# main.net
KiCad netlist of a schematic drawn in Altium Designer
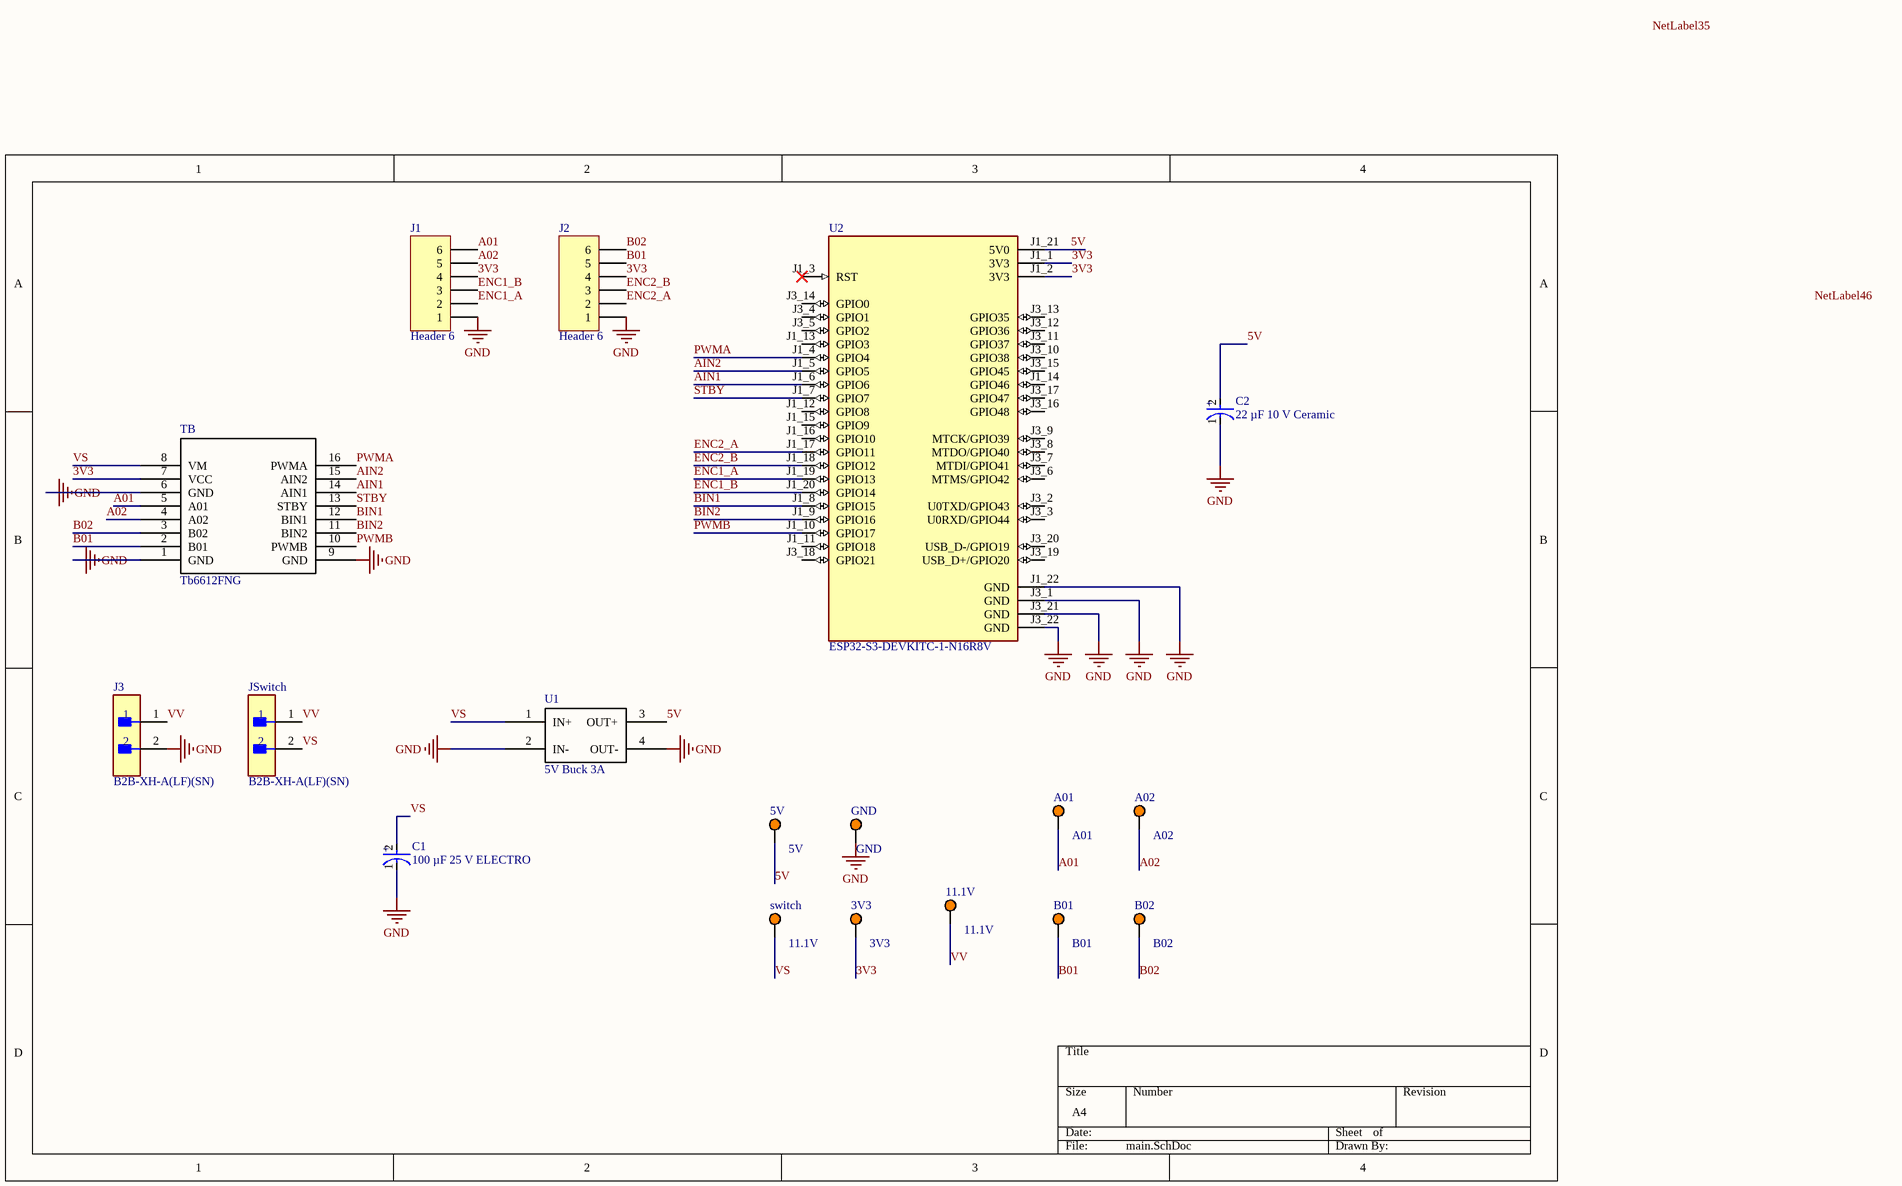
[diagram p0: main.SchDoc]

(export (version "E")
  (design (tool "Eeschema 10.0.6"))
  (components
    (comp (ref "3V3")
      (value "3V3")
      (footprint "Test-Pin-TH")
      (description "Test pin TH generic")
      (libsource (lib "UGs@UoA") (part "Test Pin"))
    )
    (comp (ref "5V")
      (value "5V")
      (footprint "Test-Pin-TH")
      (description "Test pin TH generic")
      (libsource (lib "UGs@UoA") (part "Test Pin"))
    )
    (comp (ref "11.1V")
      (value "11.1V")
      (footprint "Test-Pin-TH")
      (description "Test pin TH generic")
      (libsource (lib "UGs@UoA") (part "Test Pin"))
    )
    (comp (ref "A01")
      (value "A01")
      (footprint "Test-Pin-TH")
      (description "Test pin TH generic")
      (libsource (lib "UGs@UoA") (part "Test Pin"))
    )
    (comp (ref "A02")
      (value "A02")
      (footprint "Test-Pin-TH")
      (description "Test pin TH generic")
      (libsource (lib "UGs@UoA") (part "Test Pin"))
    )
    (comp (ref "B01")
      (value "B01")
      (footprint "Test-Pin-TH")
      (description "Test pin TH generic")
      (libsource (lib "UGs@UoA") (part "Test Pin"))
    )
    (comp (ref "B02")
      (value "B02")
      (footprint "Test-Pin-TH")
      (description "Test pin TH generic")
      (libsource (lib "UGs@UoA") (part "Test Pin"))
    )
    (comp (ref "C1")
      (value "100 µF 25 V ELECTRO")
      (footprint "FP-RAD-TH-D_6_3_0_5-L_11-MFG")
      (description "Aluminum Electrolytic Capacitors (Radial Lead Type) 100uF ±20% 25V")
      (libsource (lib "Altium Content Vault") (part "a00bbbee19879c290e62620ae7e47b1"))
    )
    (comp (ref "C2")
      (value "22 µF 10 V Ceramic")
      (footprint "FP-RAD-TH-D_6_3_0_5-L_11-MFG")
      (description "Aluminum Electrolytic Capacitors (Radial Lead Type) 100uF ±20% 25V")
      (libsource (lib "Altium Content Vault") (part "a00bbbee19879c290e62620ae7e47b1"))
    )
    (comp (ref "GND")
      (value "GND")
      (footprint "Test-Pin-TH")
      (description "Test pin TH generic")
      (libsource (lib "UGs@UoA") (part "Test Pin"))
    )
    (comp (ref "J1")
      (value "Header 6")
      (footprint "HDR1X6")
      (description "Header, 6-Pin")
      (fields (field (name "PUBLISHER") "Altium Limited"))
      (libsource (lib "Miscellaneous Connectors") (part "Header 6"))
    )
    (comp (ref "J2")
      (value "Header 6")
      (footprint "HDR1X6")
      (description "Header, 6-Pin")
      (fields (field (name "PUBLISHER") "Altium Limited"))
      (libsource (lib "Miscellaneous Connectors") (part "Header 6"))
    )
    (comp (ref "J3")
      (value "B2B-XH-A(LF)(SN)")
      (footprint "FP-B2B-XH-A_LF_SN-MFG")
      (description "CONN HEADER VERT 2POS 2.5MM")
      (libsource (lib "Altium Content Vault") (part "3bc925449376181038e59eaffc5286c"))
    )
    (comp (ref "JSwitch")
      (value "B2B-XH-A(LF)(SN)")
      (footprint "FP-B2B-XH-A_LF_SN-MFG")
      (description "CONN HEADER VERT 2POS 2.5MM")
      (libsource (lib "Altium Content Vault") (part "3bc925449376181038e59eaffc5286c"))
    )
    (comp (ref "switch")
      (value "11.1V")
      (footprint "Test-Pin-TH")
      (description "Test pin TH generic")
      (libsource (lib "UGs@UoA") (part "Test Pin"))
    )
    (comp (ref "TB") (value "Tb6612FNG") (footprint "TB6612FNG") (libsource (lib "parts") (part "Tb6612FNG")))
    (comp (ref "U1")
      (value "5V Buck 3A")
      (footprint "BUCK_MINI_3A")
      (libsource (lib "parts") (part "BUCK_5V_3A"))
    )
    (comp (ref "U2")
      (value "ESP32-S3-DEVKITC-1-N16R8V")
      (footprint "XCVR_ESP32-S3-DEVKITC-1-N16R8V")
      (fields (field (name "MF") "Espressif Systems"))
      (libsource (lib "ESP32-S3-DEVKITC-1-N16R8V") (part "ESP32-S3-DEVKITC-1-N16R8V"))
    )
  )
  (nets
    (net (code "1") (name "/3V3") (class "Default")
      (node (ref "3V3") (pin "1") (pinfunction "1_1") (pintype "passive"))
      (node (ref "J1") (pin "4") (pinfunction "4_4") (pintype "passive"))
      (node (ref "J2") (pin "4") (pinfunction "4_4") (pintype "passive"))
      (node (ref "TB") (pin "7") (pinfunction "VCC_7") (pintype "passive"))
      (node (ref "U2") (pin "J1_1") (pinfunction "3V3_J1_1") (pintype "power_in"))
      (node (ref "U2") (pin "J1_2") (pinfunction "3V3_J1_2") (pintype "power_in"))
    )
    (net (code "2") (name "/5V") (class "Default")
      (node (ref "5V") (pin "1") (pinfunction "1_1") (pintype "passive"))
      (node (ref "C2") (pin "2") (pinfunction "A_2") (pintype "passive"))
      (node (ref "U1") (pin "3") (pinfunction "OUT+_3") (pintype "passive"))
      (node (ref "U2") (pin "J1_21") (pinfunction "5V0_J1_21") (pintype "power_in"))
    )
    (net (code "3") (name "/A01") (class "Default")
      (node (ref "A01") (pin "1") (pinfunction "1_1") (pintype "passive"))
      (node (ref "J1") (pin "6") (pinfunction "6_6") (pintype "passive"))
      (node (ref "TB") (pin "5") (pinfunction "A01_5") (pintype "passive"))
    )
    (net (code "4") (name "/A02") (class "Default")
      (node (ref "A02") (pin "1") (pinfunction "1_1") (pintype "passive"))
      (node (ref "J1") (pin "5") (pinfunction "5_5") (pintype "passive"))
      (node (ref "TB") (pin "4") (pinfunction "A02_4") (pintype "passive"))
    )
    (net (code "5") (name "/AIN1") (class "Default")
      (node (ref "TB") (pin "14") (pinfunction "AIN1_14") (pintype "passive"))
      (node (ref "U2") (pin "J1_6") (pinfunction "GPIO6_J1_6") (pintype "bidirectional"))
    )
    (net (code "6") (name "/AIN2") (class "Default")
      (node (ref "TB") (pin "15") (pinfunction "AIN2_15") (pintype "passive"))
      (node (ref "U2") (pin "J1_5") (pinfunction "GPIO5_J1_5") (pintype "bidirectional"))
    )
    (net (code "7") (name "/B01") (class "Default")
      (node (ref "B01") (pin "1") (pinfunction "1_1") (pintype "passive"))
      (node (ref "J2") (pin "5") (pinfunction "5_5") (pintype "passive"))
      (node (ref "TB") (pin "2") (pinfunction "B01_2") (pintype "passive"))
    )
    (net (code "8") (name "/B02") (class "Default")
      (node (ref "B02") (pin "1") (pinfunction "1_1") (pintype "passive"))
      (node (ref "J2") (pin "6") (pinfunction "6_6") (pintype "passive"))
      (node (ref "TB") (pin "3") (pinfunction "B02_3") (pintype "passive"))
    )
    (net (code "9") (name "/BIN1") (class "Default")
      (node (ref "TB") (pin "12") (pinfunction "BIN1_12") (pintype "passive"))
      (node (ref "U2") (pin "J1_8") (pinfunction "GPIO15_J1_8") (pintype "bidirectional"))
    )
    (net (code "10") (name "/BIN2") (class "Default")
      (node (ref "TB") (pin "11") (pinfunction "BIN2_11") (pintype "passive"))
      (node (ref "U2") (pin "J1_9") (pinfunction "GPIO16_J1_9") (pintype "bidirectional"))
    )
    (net (code "11") (name "/ENC1_A") (class "Default")
      (node (ref "J1") (pin "2") (pinfunction "2_2") (pintype "passive"))
      (node (ref "U2") (pin "J1_19") (pinfunction "GPIO13_J1_19") (pintype "bidirectional"))
    )
    (net (code "12") (name "/ENC1_B") (class "Default")
      (node (ref "J1") (pin "3") (pinfunction "3_3") (pintype "passive"))
      (node (ref "U2") (pin "J1_20") (pinfunction "GPIO14_J1_20") (pintype "bidirectional"))
    )
    (net (code "13") (name "/ENC2_A") (class "Default")
      (node (ref "J2") (pin "2") (pinfunction "2_2") (pintype "passive"))
      (node (ref "U2") (pin "J1_17") (pinfunction "GPIO11_J1_17") (pintype "bidirectional"))
    )
    (net (code "14") (name "/ENC2_B") (class "Default")
      (node (ref "J2") (pin "3") (pinfunction "3_3") (pintype "passive"))
      (node (ref "U2") (pin "J1_18") (pinfunction "GPIO12_J1_18") (pintype "bidirectional"))
    )
    (net (code "17") (name "/PWMA") (class "Default")
      (node (ref "TB") (pin "16") (pinfunction "PWMA_16") (pintype "passive"))
      (node (ref "U2") (pin "J1_4") (pinfunction "GPIO4_J1_4") (pintype "bidirectional"))
    )
    (net (code "18") (name "/PWMB") (class "Default")
      (node (ref "TB") (pin "10") (pinfunction "PWMB_10") (pintype "passive"))
      (node (ref "U2") (pin "J1_10") (pinfunction "GPIO17_J1_10") (pintype "bidirectional"))
    )
    (net (code "19") (name "/STBY") (class "Default")
      (node (ref "TB") (pin "13") (pinfunction "STBY_13") (pintype "passive"))
      (node (ref "U2") (pin "J1_7") (pinfunction "GPIO7_J1_7") (pintype "bidirectional"))
    )
    (net (code "20") (name "/VS") (class "Default")
      (node (ref "C1") (pin "2") (pinfunction "A_2") (pintype "passive"))
      (node (ref "JSwitch") (pin "2") (pinfunction "2_2") (pintype "passive"))
      (node (ref "TB") (pin "8") (pinfunction "VM_8") (pintype "passive"))
      (node (ref "U1") (pin "1") (pinfunction "IN+_1") (pintype "passive"))
      (node (ref "switch") (pin "1") (pinfunction "1_1") (pintype "passive"))
    )
    (net (code "21") (name "/VV") (class "Default")
      (node (ref "11.1V") (pin "1") (pinfunction "1_1") (pintype "passive"))
      (node (ref "J3") (pin "1") (pinfunction "1_1") (pintype "passive"))
      (node (ref "JSwitch") (pin "1") (pinfunction "1_1") (pintype "passive"))
    )
    (net (code "22") (name "GND") (class "Default")
      (node (ref "C1") (pin "1") (pinfunction "C_1") (pintype "passive"))
      (node (ref "C2") (pin "1") (pinfunction "C_1") (pintype "passive"))
      (node (ref "GND") (pin "1") (pinfunction "1_1") (pintype "passive"))
      (node (ref "J1") (pin "1") (pinfunction "1_1") (pintype "passive"))
      (node (ref "J2") (pin "1") (pinfunction "1_1") (pintype "passive"))
      (node (ref "J3") (pin "2") (pinfunction "2_2") (pintype "passive"))
      (node (ref "TB") (pin "1") (pinfunction "GND_1") (pintype "passive"))
      (node (ref "TB") (pin "6") (pinfunction "GND_6") (pintype "passive"))
      (node (ref "TB") (pin "9") (pinfunction "GND_9") (pintype "passive"))
      (node (ref "U1") (pin "2") (pinfunction "IN-_2") (pintype "passive"))
      (node (ref "U1") (pin "4") (pinfunction "OUT-_4") (pintype "passive"))
      (node (ref "U2") (pin "J1_22") (pinfunction "GND_J1_22") (pintype "power_in"))
      (node (ref "U2") (pin "J3_1") (pinfunction "GND_J3_1") (pintype "power_in"))
      (node (ref "U2") (pin "J3_21") (pinfunction "GND_J3_21") (pintype "power_in"))
      (node (ref "U2") (pin "J3_22") (pinfunction "GND_J3_22") (pintype "power_in"))
    )
    (net (code "23") (name "unconnected-(U2-GPIO0-PadJ3_14)") (class "Default")
      (node (ref "U2") (pin "J3_14") (pinfunction "GPIO0_J3_14") (pintype "bidirectional"))
    )
    (net (code "24") (name "unconnected-(U2-GPIO1-PadJ3_4)") (class "Default")
      (node (ref "U2") (pin "J3_4") (pinfunction "GPIO1_J3_4") (pintype "bidirectional"))
    )
    (net (code "25") (name "unconnected-(U2-GPIO2-PadJ3_5)") (class "Default")
      (node (ref "U2") (pin "J3_5") (pinfunction "GPIO2_J3_5") (pintype "bidirectional"))
    )
    (net (code "26") (name "unconnected-(U2-GPIO3-PadJ1_13)") (class "Default")
      (node (ref "U2") (pin "J1_13") (pinfunction "GPIO3_J1_13") (pintype "bidirectional"))
    )
    (net (code "27") (name "unconnected-(U2-GPIO8-PadJ1_12)") (class "Default")
      (node (ref "U2") (pin "J1_12") (pinfunction "GPIO8_J1_12") (pintype "bidirectional"))
    )
    (net (code "28") (name "unconnected-(U2-GPIO9-PadJ1_15)") (class "Default")
      (node (ref "U2") (pin "J1_15") (pinfunction "GPIO9_J1_15") (pintype "bidirectional"))
    )
    (net (code "29") (name "unconnected-(U2-GPIO10-PadJ1_16)") (class "Default")
      (node (ref "U2") (pin "J1_16") (pinfunction "GPIO10_J1_16") (pintype "bidirectional"))
    )
    (net (code "30") (name "unconnected-(U2-GPIO18-PadJ1_11)") (class "Default")
      (node (ref "U2") (pin "J1_11") (pinfunction "GPIO18_J1_11") (pintype "bidirectional"))
    )
    (net (code "31") (name "unconnected-(U2-GPIO21-PadJ3_18)") (class "Default")
      (node (ref "U2") (pin "J3_18") (pinfunction "GPIO21_J3_18") (pintype "bidirectional"))
    )
    (net (code "32") (name "unconnected-(U2-GPIO35-PadJ3_13)") (class "Default")
      (node (ref "U2") (pin "J3_13") (pinfunction "GPIO35_J3_13") (pintype "bidirectional"))
    )
    (net (code "33") (name "unconnected-(U2-GPIO36-PadJ3_12)") (class "Default")
      (node (ref "U2") (pin "J3_12") (pinfunction "GPIO36_J3_12") (pintype "bidirectional"))
    )
    (net (code "34") (name "unconnected-(U2-GPIO37-PadJ3_11)") (class "Default")
      (node (ref "U2") (pin "J3_11") (pinfunction "GPIO37_J3_11") (pintype "bidirectional"))
    )
    (net (code "35") (name "unconnected-(U2-GPIO38-PadJ3_10)") (class "Default")
      (node (ref "U2") (pin "J3_10") (pinfunction "GPIO38_J3_10") (pintype "bidirectional"))
    )
    (net (code "36") (name "unconnected-(U2-GPIO45-PadJ3_15)") (class "Default")
      (node (ref "U2") (pin "J3_15") (pinfunction "GPIO45_J3_15") (pintype "bidirectional"))
    )
    (net (code "37") (name "unconnected-(U2-GPIO46-PadJ1_14)") (class "Default")
      (node (ref "U2") (pin "J1_14") (pinfunction "GPIO46_J1_14") (pintype "bidirectional"))
    )
    (net (code "38") (name "unconnected-(U2-GPIO47-PadJ3_17)") (class "Default")
      (node (ref "U2") (pin "J3_17") (pinfunction "GPIO47_J3_17") (pintype "bidirectional"))
    )
    (net (code "39") (name "unconnected-(U2-GPIO48-PadJ3_16)") (class "Default")
      (node (ref "U2") (pin "J3_16") (pinfunction "GPIO48_J3_16") (pintype "bidirectional"))
    )
    (net (code "40") (name "unconnected-(U2-MTCK{slash}GPIO39-PadJ3_9)") (class "Default")
      (node (ref "U2") (pin "J3_9") (pinfunction "MTCK/GPIO39_J3_9") (pintype "bidirectional"))
    )
    (net (code "41") (name "unconnected-(U2-MTDI{slash}GPIO41-PadJ3_7)") (class "Default")
      (node (ref "U2") (pin "J3_7") (pinfunction "MTDI/GPIO41_J3_7") (pintype "bidirectional"))
    )
    (net (code "42") (name "unconnected-(U2-MTDO{slash}GPIO40-PadJ3_8)") (class "Default")
      (node (ref "U2") (pin "J3_8") (pinfunction "MTDO/GPIO40_J3_8") (pintype "bidirectional"))
    )
    (net (code "43") (name "unconnected-(U2-MTMS{slash}GPIO42-PadJ3_6)") (class "Default")
      (node (ref "U2") (pin "J3_6") (pinfunction "MTMS/GPIO42_J3_6") (pintype "bidirectional"))
    )
    (net (code "44") (name "unconnected-(U2-RST-PadJ1_3)") (class "Default")
      (node (ref "U2") (pin "J1_3") (pinfunction "RST_J1_3") (pintype "input+no_connect"))
    )
    (net (code "45") (name "unconnected-(U2-U0RXD{slash}GPIO44-PadJ3_3)") (class "Default")
      (node (ref "U2") (pin "J3_3") (pinfunction "U0RXD/GPIO44_J3_3") (pintype "bidirectional"))
    )
    (net (code "46") (name "unconnected-(U2-U0TXD{slash}GPIO43-PadJ3_2)") (class "Default")
      (node (ref "U2") (pin "J3_2") (pinfunction "U0TXD/GPIO43_J3_2") (pintype "bidirectional"))
    )
    (net (code "47") (name "unconnected-(U2-USB_D+{slash}GPIO20-PadJ3_19)") (class "Default")
      (node (ref "U2") (pin "J3_19") (pinfunction "USB_D+/GPIO20_J3_19") (pintype "bidirectional"))
    )
    (net (code "48") (name "unconnected-(U2-USB_D-{slash}GPIO19-PadJ3_20)") (class "Default")
      (node (ref "U2") (pin "J3_20") (pinfunction "USB_D-/GPIO19_J3_20") (pintype "bidirectional"))
    )
  )
)
